# BLE.net
KiCad netlist of a schematic drawn in Altium Designer
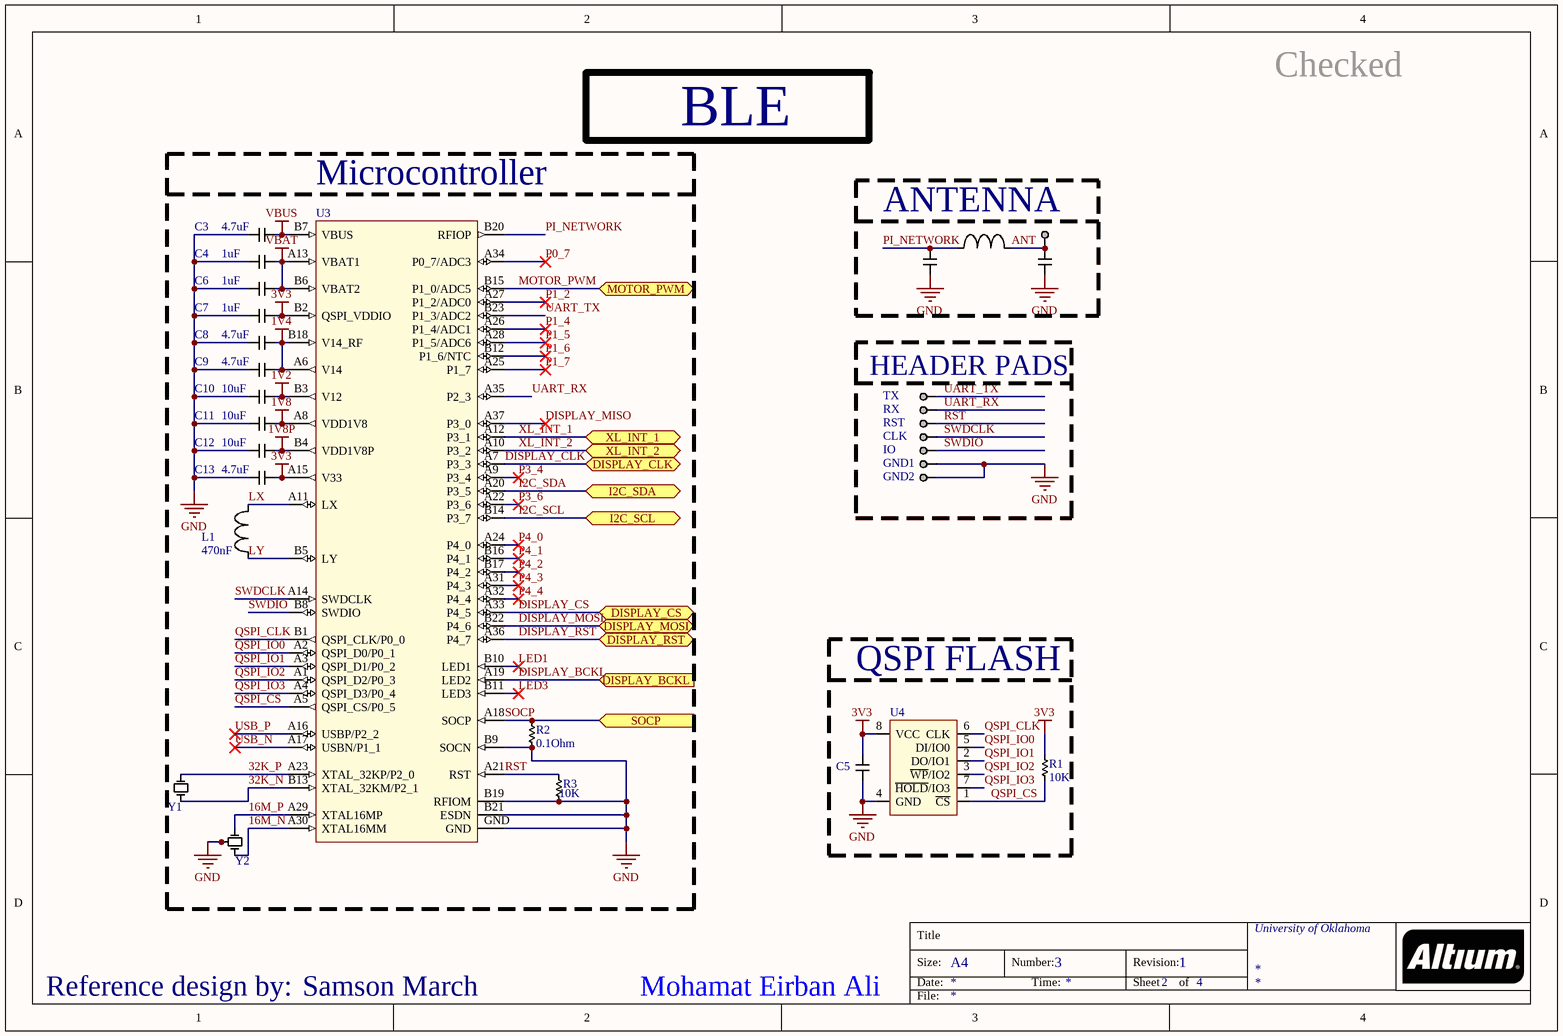
[diagram p0: BLE.SchDoc]

(export (version "E")
  (design (tool "Eeschema 10.0.6"))
  (components
    (comp (ref "ANT1")
      (value "~")
      (footprint "0.1\" Header")
      (description "0.1\" Header")
      (libsource (lib "smarchWatch_V5") (part "0.1{dblquote} Header"))
    )
    (comp (ref "C3")
      (value "4.7uF")
      (footprint "CAP_0603_HIGH")
      (description "0603 Capacitor")
      (libsource (lib "smarchWatch_V5") (part "Capacitor_0603_2"))
    )
    (comp (ref "C4")
      (value "1uF")
      (footprint "CAP_0603_HIGH")
      (description "0603 Capacitor")
      (libsource (lib "smarchWatch_V5") (part "Capacitor_0603_3"))
    )
    (comp (ref "C5")
      (value "~")
      (footprint "CAP_0603_HIGH")
      (description "0603 Capacitor")
      (libsource (lib "smarchWatch_V5") (part "Capacitor_0603"))
    )
    (comp (ref "C6")
      (value "1uF")
      (footprint "CAP_0603_HIGH")
      (description "0603 Capacitor")
      (libsource (lib "smarchWatch_V5") (part "Capacitor_0603_3"))
    )
    (comp (ref "C7")
      (value "1uF")
      (footprint "CAP_0603_HIGH")
      (description "0603 Capacitor")
      (libsource (lib "smarchWatch_V5") (part "Capacitor_0603_3"))
    )
    (comp (ref "C8")
      (value "4.7uF")
      (footprint "CAP_0603_HIGH")
      (description "0603 Capacitor")
      (libsource (lib "smarchWatch_V5") (part "Capacitor_0603_2"))
    )
    (comp (ref "C9")
      (value "4.7uF")
      (footprint "CAP_0603_HIGH")
      (description "0603 Capacitor")
      (libsource (lib "smarchWatch_V5") (part "Capacitor_0603_2"))
    )
    (comp (ref "C10")
      (value "10uF")
      (footprint "CAP_0603_HIGH")
      (description "0603 Capacitor")
      (libsource (lib "smarchWatch_V5") (part "Capacitor_0603_1"))
    )
    (comp (ref "C11")
      (value "10uF")
      (footprint "CAP_0603_HIGH")
      (description "0603 Capacitor")
      (libsource (lib "smarchWatch_V5") (part "Capacitor_0603_1"))
    )
    (comp (ref "C12")
      (value "10uF")
      (footprint "CAP_0603_HIGH")
      (description "0603 Capacitor")
      (libsource (lib "smarchWatch_V5") (part "Capacitor_0603_1"))
    )
    (comp (ref "C13")
      (value "4.7uF")
      (footprint "CAP_0603_HIGH")
      (description "0603 Capacitor")
      (libsource (lib "smarchWatch_V5") (part "Capacitor_0603_2"))
    )
    (comp (ref "C16")
      (value "~")
      (footprint "CAP_0402_MEDIUM")
      (description "0402 Capacitor")
      (libsource (lib "smarchWatch_V5") (part "Capacitor_0402"))
    )
    (comp (ref "C17")
      (value "~")
      (footprint "CAP_0402_MEDIUM")
      (description "0402 Capacitor")
      (libsource (lib "smarchWatch_V5") (part "Capacitor_0402"))
    )
    (comp (ref "CLK")
      (value "~")
      (footprint "0.1\" Pad")
      (description "0.1\" Pad")
      (libsource (lib "smarchWatch_V5") (part "0.1{dblquote} Pad"))
    )
    (comp (ref "GND1")
      (value "~")
      (footprint "0.1\" Pad")
      (description "0.1\" Pad")
      (libsource (lib "smarchWatch_V5") (part "0.1{dblquote} Pad"))
    )
    (comp (ref "GND2")
      (value "~")
      (footprint "0.1\" Pad")
      (description "0.1\" Pad")
      (libsource (lib "smarchWatch_V5") (part "0.1{dblquote} Pad"))
    )
    (comp (ref "IO")
      (value "~")
      (footprint "0.1\" Pad")
      (description "0.1\" Pad")
      (libsource (lib "smarchWatch_V5") (part "0.1{dblquote} Pad"))
    )
    (comp (ref "L1")
      (value "470nF")
      (footprint "IND_0805_HIGH")
      (description "Inductor_0805")
      (libsource (lib "smarchWatch_V5") (part "Inductor_0805"))
    )
    (comp (ref "L2")
      (value "~")
      (footprint "IND_0402_MEDIUM")
      (description "Inductor_0402")
      (libsource (lib "smarchWatch_V5") (part "Inductor_0402"))
    )
    (comp (ref "R1")
      (value "10K")
      (footprint "RES_0603_HIGH")
      (description "0603 Resistor")
      (libsource (lib "smarchWatch_V5") (part "Resistor_0603_3"))
    )
    (comp (ref "R2")
      (value "0.1Ohm")
      (footprint "RES_0603_HIGH")
      (description "0603 Resistor")
      (libsource (lib "smarchWatch_V5") (part "Resistor_0603_4"))
    )
    (comp (ref "R3")
      (value "10K")
      (footprint "RES_0603_HIGH")
      (description "0603 Resistor")
      (libsource (lib "smarchWatch_V5") (part "Resistor_0603_3"))
    )
    (comp (ref "RST")
      (value "~")
      (footprint "0.1\" Pad")
      (description "0.1\" Pad")
      (libsource (lib "smarchWatch_V5") (part "0.1{dblquote} Pad"))
    )
    (comp (ref "RX")
      (value "~")
      (footprint "0.1\" Pad")
      (description "0.1\" Pad")
      (libsource (lib "smarchWatch_V5") (part "0.1{dblquote} Pad"))
    )
    (comp (ref "TX")
      (value "~")
      (footprint "0.1\" Pad")
      (description "0.1\" Pad")
      (libsource (lib "smarchWatch_V5") (part "0.1{dblquote} Pad"))
    )
    (comp (ref "U3")
      (value "~")
      (footprint "DA14683")
      (description "SmartBond DA14683 Single-chip high-security Bluetooth 5 solution with expandable memory")
      (libsource (lib "smarchWatch_V5") (part "DA14683"))
    )
    (comp (ref "U4")
      (value "~")
      (footprint "W25Q128JVPIQ")
      (description "FLASH - NOR Memory IC 128Mb (16M x 8) SPI - Quad I/O, QPI, DTR 133MHz  8-WSON (6x5)")
      (libsource (lib "smarchWatch_V5") (part "W25Q128JVPIQ"))
    )
    (comp (ref "Y1")
      (value "~")
      (footprint "9HT11-32.768KDZB-T")
      (description "32.768kHz ±20ppm Crystal 6pF 90 kOhms 2-SMD, No Lead")
      (libsource (lib "smarchWatch_V5") (part "9HT11-32.768KDZB-T"))
    )
    (comp (ref "Y2")
      (value "~")
      (footprint "7M-16.000MEEQ-T")
      (description "16MHz ±10ppm Crystal 10pF 80 Ohms 4-SMD, No Lead")
      (libsource (lib "smarchWatch_V5") (part "7M-16.000MEEQ-T"))
    )
  )
  (nets
    (net (code "1") (name "/16M_N") (class "Default")
      (node (ref "U3") (pin "A30") (pinfunction "XTAL16MM_A30") (pintype "input"))
      (node (ref "Y2") (pin "3") (pinfunction "3_3") (pintype "passive"))
    )
    (net (code "2") (name "/16M_P") (class "Default")
      (node (ref "U3") (pin "A29") (pinfunction "XTAL16MP_A29") (pintype "input"))
      (node (ref "Y2") (pin "1") (pinfunction "1_1") (pintype "passive"))
    )
    (net (code "3") (name "/32K_N") (class "Default")
      (node (ref "U3") (pin "B13") (pinfunction "XTAL_32KM/P2_1_B13") (pintype "input"))
      (node (ref "Y1") (pin "1") (pinfunction "1_1") (pintype "passive"))
    )
    (net (code "4") (name "/32K_P") (class "Default")
      (node (ref "U3") (pin "A23") (pinfunction "XTAL_32KP/P2_0_A23") (pintype "input"))
      (node (ref "Y1") (pin "2") (pinfunction "2_2") (pintype "passive"))
    )
    (net (code "5") (name "/ANT") (class "Default")
      (node (ref "ANT1") (pin "1") (pinfunction "1_1") (pintype "passive"))
      (node (ref "C17") (pin "2") (pinfunction "2_2") (pintype "passive"))
      (node (ref "L2") (pin "1") (pinfunction "1_1") (pintype "passive"))
    )
    (net (code "6") (name "/DISPLAY_BCKL") (class "Default")
      (node (ref "U3") (pin "A19") (pinfunction "LED2_A19") (pintype "input"))
    )
    (net (code "7") (name "/DISPLAY_CLK") (class "Default")
      (node (ref "U3") (pin "A7") (pinfunction "P3_3_A7") (pintype "bidirectional"))
    )
    (net (code "8") (name "/DISPLAY_CS") (class "Default")
      (node (ref "U3") (pin "A33") (pinfunction "P4_5_A33") (pintype "bidirectional"))
    )
    (net (code "9") (name "/DISPLAY_MISO") (class "Default")
      (node (ref "U3") (pin "A37") (pinfunction "P3_0_A37") (pintype "bidirectional+no_connect"))
    )
    (net (code "10") (name "/DISPLAY_MOSI") (class "Default")
      (node (ref "U3") (pin "B22") (pinfunction "P4_6_B22") (pintype "bidirectional"))
    )
    (net (code "11") (name "/DISPLAY_RST") (class "Default")
      (node (ref "U3") (pin "A36") (pinfunction "P4_7_A36") (pintype "bidirectional"))
    )
    (net (code "12") (name "/I2C_SCL") (class "Default")
      (node (ref "U3") (pin "B14") (pinfunction "P3_7_B14") (pintype "bidirectional"))
    )
    (net (code "13") (name "/I2C_SDA") (class "Default")
      (node (ref "U3") (pin "A20") (pinfunction "P3_5_A20") (pintype "bidirectional"))
    )
    (net (code "14") (name "/LED1") (class "Default")
      (node (ref "U3") (pin "B10") (pinfunction "LED1_B10") (pintype "input+no_connect"))
    )
    (net (code "15") (name "/LED3") (class "Default")
      (node (ref "U3") (pin "B11") (pinfunction "LED3_B11") (pintype "input+no_connect"))
    )
    (net (code "16") (name "/LX") (class "Default")
      (node (ref "L1") (pin "2") (pinfunction "2_2") (pintype "passive"))
      (node (ref "U3") (pin "A11") (pinfunction "LX_A11") (pintype "bidirectional"))
    )
    (net (code "17") (name "/LY") (class "Default")
      (node (ref "L1") (pin "1") (pinfunction "1_1") (pintype "passive"))
      (node (ref "U3") (pin "B5") (pinfunction "LY_B5") (pintype "bidirectional"))
    )
    (net (code "18") (name "/MOTOR_PWM") (class "Default")
      (node (ref "U3") (pin "B15") (pinfunction "P1_0/ADC5_B15") (pintype "bidirectional"))
    )
    (net (code "19") (name "/P0_7") (class "Default")
      (node (ref "U3") (pin "A34") (pinfunction "P0_7/ADC3_A34") (pintype "bidirectional+no_connect"))
    )
    (net (code "20") (name "/P1_2") (class "Default")
      (node (ref "U3") (pin "A27") (pinfunction "P1_2/ADC0_A27") (pintype "bidirectional+no_connect"))
    )
    (net (code "21") (name "/P1_4") (class "Default")
      (node (ref "U3") (pin "A26") (pinfunction "P1_4/ADC1_A26") (pintype "bidirectional+no_connect"))
    )
    (net (code "22") (name "/P1_5") (class "Default")
      (node (ref "U3") (pin "A28") (pinfunction "P1_5/ADC6_A28") (pintype "bidirectional+no_connect"))
    )
    (net (code "23") (name "/P1_6") (class "Default")
      (node (ref "U3") (pin "B12") (pinfunction "P1_6/NTC_B12") (pintype "bidirectional+no_connect"))
    )
    (net (code "24") (name "/P1_7") (class "Default")
      (node (ref "U3") (pin "A25") (pinfunction "P1_7_A25") (pintype "bidirectional+no_connect"))
    )
    (net (code "25") (name "/P3_4") (class "Default")
      (node (ref "U3") (pin "A9") (pinfunction "P3_4_A9") (pintype "bidirectional+no_connect"))
    )
    (net (code "26") (name "/P3_6") (class "Default")
      (node (ref "U3") (pin "A22") (pinfunction "P3_6_A22") (pintype "bidirectional+no_connect"))
    )
    (net (code "27") (name "/P4_0") (class "Default")
      (node (ref "U3") (pin "A24") (pinfunction "P4_0_A24") (pintype "bidirectional+no_connect"))
    )
    (net (code "28") (name "/P4_1") (class "Default")
      (node (ref "U3") (pin "B16") (pinfunction "P4_1_B16") (pintype "bidirectional+no_connect"))
    )
    (net (code "29") (name "/P4_2") (class "Default")
      (node (ref "U3") (pin "B17") (pinfunction "P4_2_B17") (pintype "bidirectional+no_connect"))
    )
    (net (code "30") (name "/P4_3") (class "Default")
      (node (ref "U3") (pin "A31") (pinfunction "P4_3_A31") (pintype "bidirectional+no_connect"))
    )
    (net (code "31") (name "/P4_4") (class "Default")
      (node (ref "U3") (pin "A32") (pinfunction "P4_4_A32") (pintype "bidirectional+no_connect"))
    )
    (net (code "32") (name "/PI_NETWORK") (class "Default")
      (node (ref "C16") (pin "2") (pinfunction "2_2") (pintype "passive"))
      (node (ref "L2") (pin "2") (pinfunction "2_2") (pintype "passive"))
      (node (ref "U3") (pin "B20") (pinfunction "RFIOP_B20") (pintype "output"))
    )
    (net (code "33") (name "/QSPI_CLK") (class "Default")
      (node (ref "U3") (pin "B1") (pinfunction "QSPI_CLK/P0_0_B1") (pintype "output"))
      (node (ref "U4") (pin "6") (pinfunction "CLK_6") (pintype "passive"))
    )
    (net (code "34") (name "/QSPI_CS") (class "Default")
      (node (ref "R1") (pin "1") (pinfunction "1_1") (pintype "passive"))
      (node (ref "U3") (pin "A5") (pinfunction "QSPI_CS/P0_5_A5") (pintype "output"))
      (node (ref "U4") (pin "1") (pinfunction "~{CS}_1") (pintype "passive"))
    )
    (net (code "35") (name "/QSPI_IO0") (class "Default")
      (node (ref "U3") (pin "A2") (pinfunction "QSPI_D0/P0_1_A2") (pintype "bidirectional"))
      (node (ref "U4") (pin "5") (pinfunction "DI/IO0_5") (pintype "passive"))
    )
    (net (code "36") (name "/QSPI_IO1") (class "Default")
      (node (ref "U3") (pin "A3") (pinfunction "QSPI_D1/P0_2_A3") (pintype "bidirectional"))
      (node (ref "U4") (pin "2") (pinfunction "DO/IO1_2") (pintype "passive"))
    )
    (net (code "37") (name "/QSPI_IO2") (class "Default")
      (node (ref "U3") (pin "A1") (pinfunction "QSPI_D2/P0_3_A1") (pintype "bidirectional"))
      (node (ref "U4") (pin "3") (pinfunction "~{WP}/IO2_3") (pintype "passive"))
    )
    (net (code "38") (name "/QSPI_IO3") (class "Default")
      (node (ref "U3") (pin "A4") (pinfunction "QSPI_D3/P0_4_A4") (pintype "bidirectional"))
      (node (ref "U4") (pin "7") (pinfunction "~{HOLD}/IO3_7") (pintype "passive"))
    )
    (net (code "39") (name "/RST") (class "Default")
      (node (ref "R3") (pin "2") (pinfunction "2_2") (pintype "passive"))
      (node (ref "RST") (pin "1") (pinfunction "1_1") (pintype "passive"))
      (node (ref "U3") (pin "A21") (pinfunction "RST_A21") (pintype "input"))
    )
    (net (code "40") (name "/SOCP") (class "Default")
      (node (ref "R2") (pin "2") (pinfunction "2_2") (pintype "passive"))
      (node (ref "U3") (pin "A18") (pinfunction "SOCP_A18") (pintype "input"))
    )
    (net (code "41") (name "/SWDCLK") (class "Default")
      (node (ref "CLK") (pin "1") (pinfunction "1_1") (pintype "passive"))
      (node (ref "U3") (pin "A14") (pinfunction "SWDCLK_A14") (pintype "input"))
    )
    (net (code "42") (name "/SWDIO") (class "Default")
      (node (ref "IO") (pin "1") (pinfunction "1_1") (pintype "passive"))
      (node (ref "U3") (pin "B8") (pinfunction "SWDIO_B8") (pintype "bidirectional"))
    )
    (net (code "43") (name "/UART_RX") (class "Default")
      (node (ref "RX") (pin "1") (pinfunction "1_1") (pintype "passive"))
      (node (ref "U3") (pin "A35") (pinfunction "P2_3_A35") (pintype "bidirectional"))
    )
    (net (code "44") (name "/UART_TX") (class "Default")
      (node (ref "TX") (pin "1") (pinfunction "1_1") (pintype "passive"))
      (node (ref "U3") (pin "B23") (pinfunction "P1_3/ADC2_B23") (pintype "bidirectional"))
    )
    (net (code "45") (name "/USB_N") (class "Default")
      (node (ref "U3") (pin "A17") (pinfunction "USBN/P1_1_A17") (pintype "bidirectional+no_connect"))
    )
    (net (code "46") (name "/USB_P") (class "Default")
      (node (ref "U3") (pin "A16") (pinfunction "USBP/P2_2_A16") (pintype "bidirectional+no_connect"))
    )
    (net (code "47") (name "/XL_INT_1") (class "Default")
      (node (ref "U3") (pin "A12") (pinfunction "P3_1_A12") (pintype "bidirectional"))
    )
    (net (code "48") (name "/XL_INT_2") (class "Default")
      (node (ref "U3") (pin "A10") (pinfunction "P3_2_A10") (pintype "bidirectional"))
    )
    (net (code "49") (name "1V2") (class "Default")
      (node (ref "C10") (pin "1") (pinfunction "1_1") (pintype "passive"))
      (node (ref "U3") (pin "B3") (pinfunction "V12_B3") (pintype "output"))
    )
    (net (code "50") (name "1V4") (class "Default")
      (node (ref "C8") (pin "1") (pinfunction "1_1") (pintype "passive"))
      (node (ref "C9") (pin "1") (pinfunction "1_1") (pintype "passive"))
      (node (ref "U3") (pin "A6") (pinfunction "V14_A6") (pintype "output"))
      (node (ref "U3") (pin "B18") (pinfunction "V14_RF_B18") (pintype "input"))
    )
    (net (code "51") (name "1V8") (class "Default")
      (node (ref "C11") (pin "1") (pinfunction "1_1") (pintype "passive"))
      (node (ref "U3") (pin "A8") (pinfunction "VDD1V8_A8") (pintype "output"))
    )
    (net (code "52") (name "1V8P") (class "Default")
      (node (ref "C12") (pin "1") (pinfunction "1_1") (pintype "passive"))
      (node (ref "U3") (pin "B4") (pinfunction "VDD1V8P_B4") (pintype "output"))
    )
    (net (code "53") (name "3V3") (class "Default")
      (node (ref "C13") (pin "1") (pinfunction "1_1") (pintype "passive"))
      (node (ref "C5") (pin "1") (pinfunction "1_1") (pintype "passive"))
      (node (ref "C7") (pin "1") (pinfunction "1_1") (pintype "passive"))
      (node (ref "R1") (pin "2") (pinfunction "2_2") (pintype "passive"))
      (node (ref "U3") (pin "A15") (pinfunction "V33_A15") (pintype "output"))
      (node (ref "U3") (pin "B2") (pinfunction "QSPI_VDDIO_B2") (pintype "input"))
      (node (ref "U4") (pin "8") (pinfunction "VCC_8") (pintype "passive"))
    )
    (net (code "54") (name "GND") (class "Default")
      (node (ref "C10") (pin "2") (pinfunction "2_2") (pintype "passive"))
      (node (ref "C11") (pin "2") (pinfunction "2_2") (pintype "passive"))
      (node (ref "C12") (pin "2") (pinfunction "2_2") (pintype "passive"))
      (node (ref "C13") (pin "2") (pinfunction "2_2") (pintype "passive"))
      (node (ref "C16") (pin "1") (pinfunction "1_1") (pintype "passive"))
      (node (ref "C17") (pin "1") (pinfunction "1_1") (pintype "passive"))
      (node (ref "C3") (pin "2") (pinfunction "2_2") (pintype "passive"))
      (node (ref "C4") (pin "2") (pinfunction "2_2") (pintype "passive"))
      (node (ref "C5") (pin "2") (pinfunction "2_2") (pintype "passive"))
      (node (ref "C6") (pin "2") (pinfunction "2_2") (pintype "passive"))
      (node (ref "C7") (pin "2") (pinfunction "2_2") (pintype "passive"))
      (node (ref "C8") (pin "2") (pinfunction "2_2") (pintype "passive"))
      (node (ref "C9") (pin "2") (pinfunction "2_2") (pintype "passive"))
      (node (ref "GND1") (pin "1") (pinfunction "1_1") (pintype "passive"))
      (node (ref "GND2") (pin "1") (pinfunction "1_1") (pintype "passive"))
      (node (ref "R2") (pin "1") (pinfunction "1_1") (pintype "passive"))
      (node (ref "R3") (pin "1") (pinfunction "1_1") (pintype "passive"))
      (node (ref "U3") (pin "B19") (pinfunction "RFIOM_B19") (pintype "power_in"))
      (node (ref "U3") (pin "B21") (pinfunction "ESDN_B21") (pintype "power_in"))
      (node (ref "U3") (pin "B9") (pinfunction "SOCN_B9") (pintype "input"))
      (node (ref "U3") (pin "GND") (pinfunction "GND_GND") (pintype "power_in"))
      (node (ref "U4") (pin "4") (pinfunction "GND_4") (pintype "passive"))
      (node (ref "Y2") (pin "2") (pinfunction "2_2") (pintype "passive"))
      (node (ref "Y2") (pin "4") (pinfunction "4_4") (pintype "passive"))
    )
    (net (code "55") (name "VBAT") (class "Default")
      (node (ref "C4") (pin "1") (pinfunction "1_1") (pintype "passive"))
      (node (ref "C6") (pin "1") (pinfunction "1_1") (pintype "passive"))
      (node (ref "U3") (pin "A13") (pinfunction "VBAT1_A13") (pintype "input"))
      (node (ref "U3") (pin "B6") (pinfunction "VBAT2_B6") (pintype "input"))
    )
    (net (code "56") (name "VBUS") (class "Default")
      (node (ref "C3") (pin "1") (pinfunction "1_1") (pintype "passive"))
      (node (ref "U3") (pin "B7") (pinfunction "VBUS_B7") (pintype "input"))
    )
  )
)
